# DoubleAmp.net
KiCad netlist of a schematic drawn in EAGLE
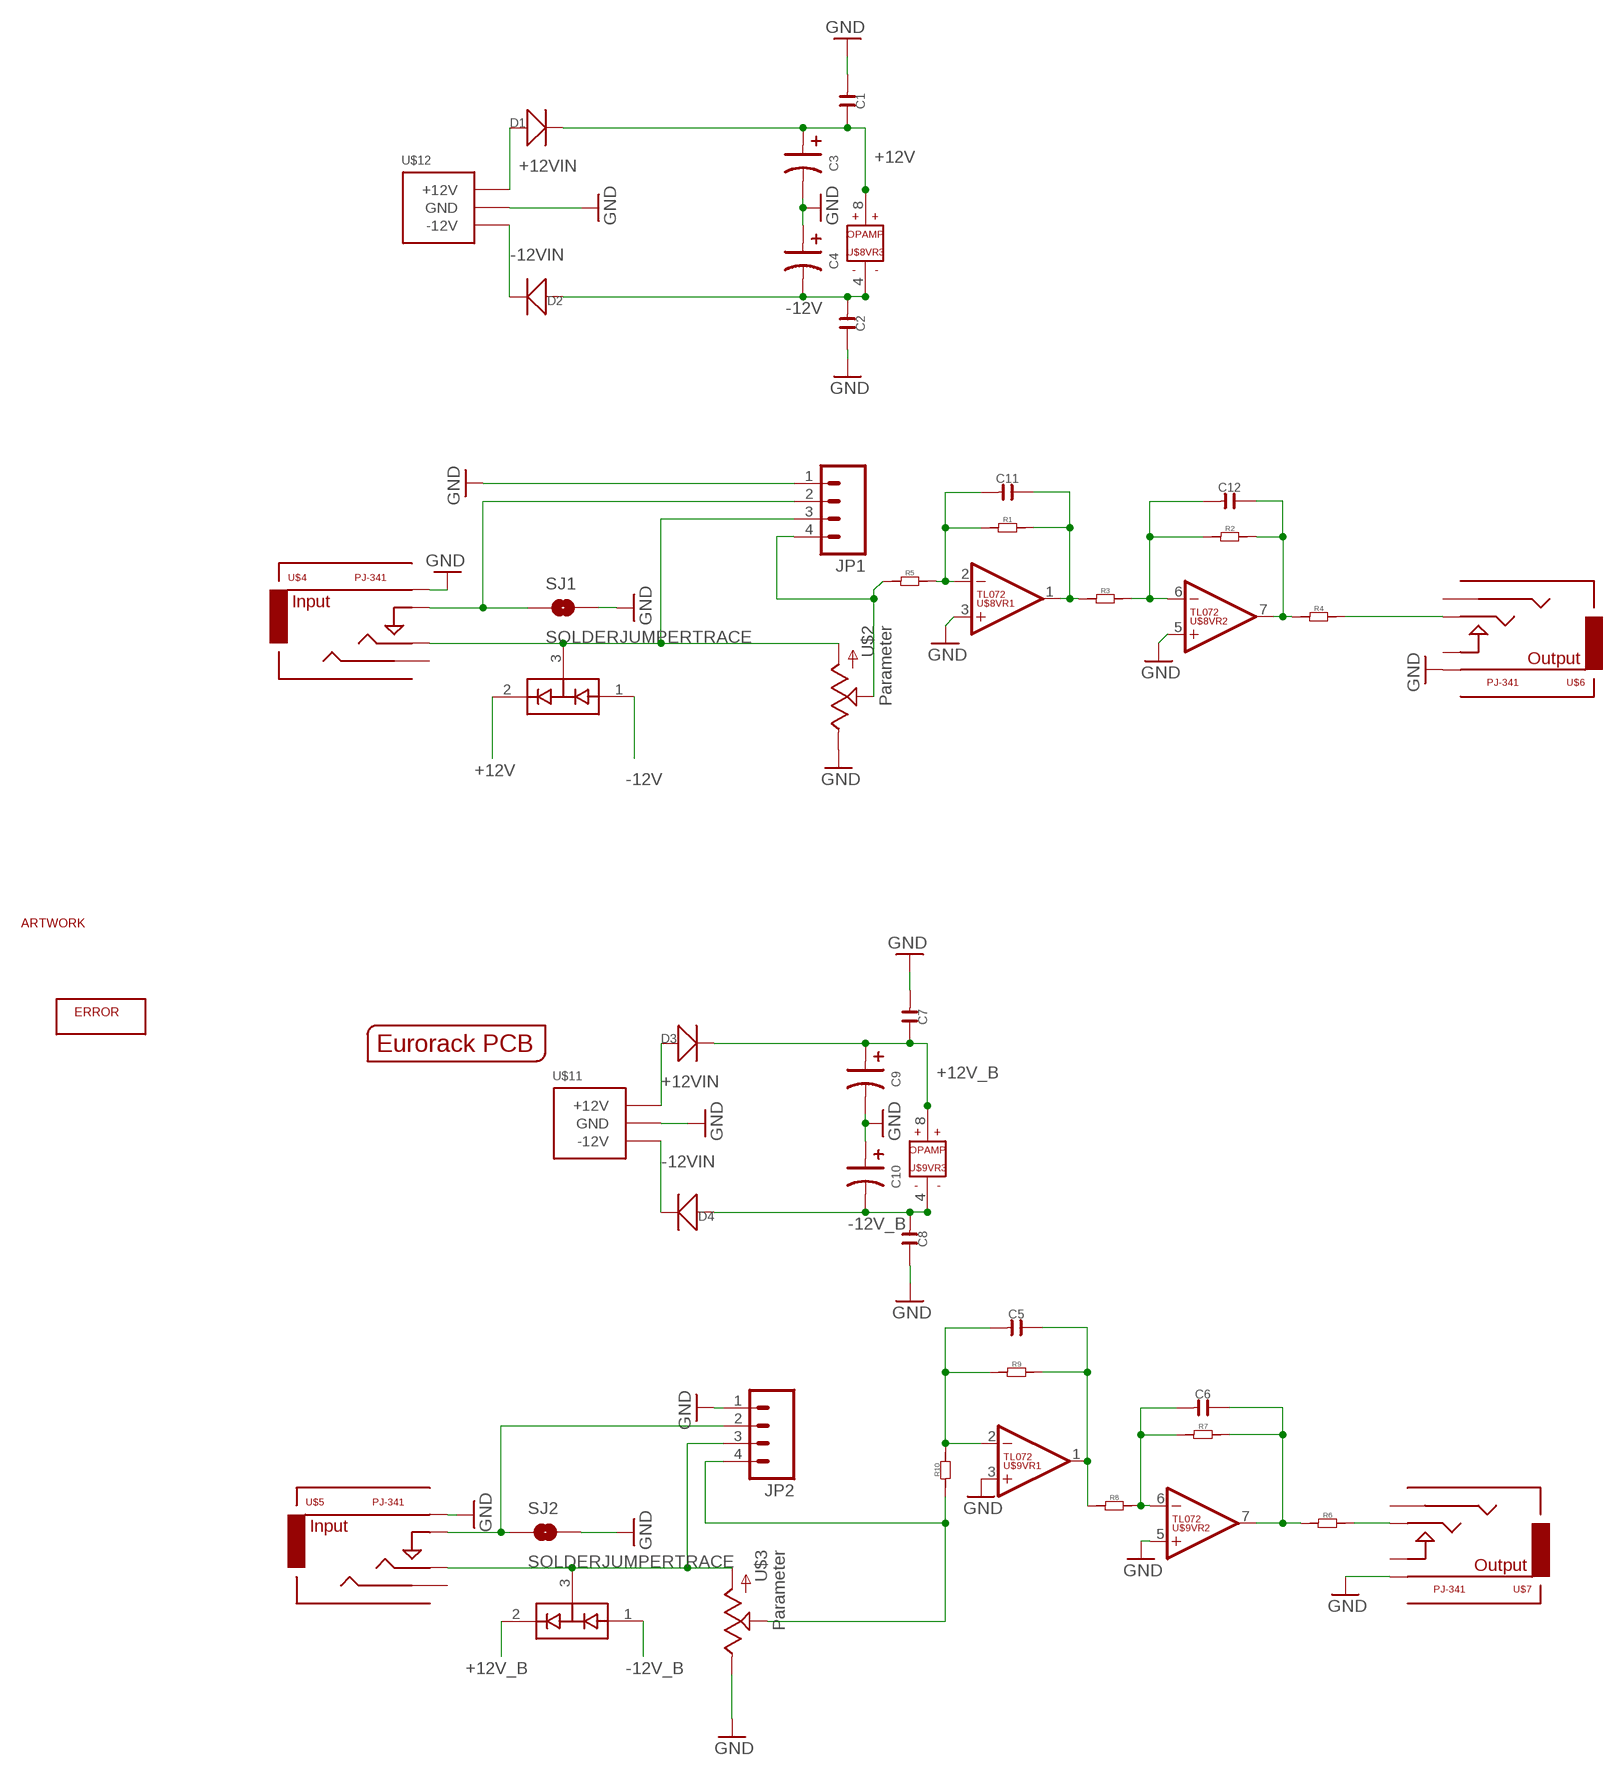
[diagram p0: schematic, sheet 1]

(export (version "E")
  (design (tool "Eeschema 10.0.6"))
  (components
    (comp (ref "C1")
      (value "C-0603")
      (footprint "eagle-import:C0603")
      (libsource (lib "eagle-import") (part "C-0603"))
    )
    (comp (ref "C2")
      (value "C-0603")
      (footprint "eagle-import:C0603")
      (libsource (lib "eagle-import") (part "C-0603"))
    )
    (comp (ref "C3")
      (value "C-POLAR-A")
      (footprint "eagle-import:AVX-A")
      (libsource (lib "eagle-import") (part "C-POLAR-A"))
    )
    (comp (ref "C4")
      (value "C-POLAR-A")
      (footprint "eagle-import:AVX-A")
      (libsource (lib "eagle-import") (part "C-POLAR-A"))
    )
    (comp (ref "C5")
      (value "C-0603")
      (footprint "eagle-import:C0603")
      (libsource (lib "eagle-import") (part "C-0603"))
    )
    (comp (ref "C6")
      (value "C-0603")
      (footprint "eagle-import:C0603")
      (libsource (lib "eagle-import") (part "C-0603"))
    )
    (comp (ref "C7")
      (value "C-0603")
      (footprint "eagle-import:C0603")
      (libsource (lib "eagle-import") (part "C-0603"))
    )
    (comp (ref "C8")
      (value "C-0603")
      (footprint "eagle-import:C0603")
      (libsource (lib "eagle-import") (part "C-0603"))
    )
    (comp (ref "C9")
      (value "C-POLAR-A")
      (footprint "eagle-import:AVX-A")
      (libsource (lib "eagle-import") (part "C-POLAR-A"))
    )
    (comp (ref "C10")
      (value "C-POLAR-A")
      (footprint "eagle-import:AVX-A")
      (libsource (lib "eagle-import") (part "C-POLAR-A"))
    )
    (comp (ref "C11")
      (value "C-0603")
      (footprint "eagle-import:C0603")
      (libsource (lib "eagle-import") (part "C-0603"))
    )
    (comp (ref "C12")
      (value "C-0603")
      (footprint "eagle-import:C0603")
      (libsource (lib "eagle-import") (part "C-0603"))
    )
    (comp (ref "D1")
      (value "D-SMA")
      (footprint "eagle-import:DO-214AC")
      (libsource (lib "eagle-import") (part "D-SMA"))
    )
    (comp (ref "D2")
      (value "D-SMA")
      (footprint "eagle-import:DO-214AC")
      (libsource (lib "eagle-import") (part "D-SMA"))
    )
    (comp (ref "D3")
      (value "D-SMA")
      (footprint "eagle-import:DO-214AC")
      (libsource (lib "eagle-import") (part "D-SMA"))
    )
    (comp (ref "D4")
      (value "D-SMA")
      (footprint "eagle-import:DO-214AC")
      (libsource (lib "eagle-import") (part "D-SMA"))
    )
    (comp (ref "D5")
      (value "BAV99")
      (footprint "eagle-import:SOT23")
      (libsource (lib "eagle-import") (part "BAV99"))
    )
    (comp (ref "D6")
      (value "BAV99")
      (footprint "eagle-import:SOT23")
      (libsource (lib "eagle-import") (part "BAV99"))
    )
    (comp (ref "JP1")
      (value "M04PTH")
      (footprint "eagle-import:1X04")
      (libsource (lib "eagle-import") (part "M04PTH"))
    )
    (comp (ref "JP2")
      (value "M04PTH")
      (footprint "eagle-import:1X04")
      (libsource (lib "eagle-import") (part "M04PTH"))
    )
    (comp (ref "R1")
      (value "R-0603")
      (footprint "eagle-import:R0603")
      (libsource (lib "eagle-import") (part "R-0603"))
    )
    (comp (ref "R2")
      (value "R-0603")
      (footprint "eagle-import:R0603")
      (libsource (lib "eagle-import") (part "R-0603"))
    )
    (comp (ref "R3")
      (value "R-0603")
      (footprint "eagle-import:R0603")
      (libsource (lib "eagle-import") (part "R-0603"))
    )
    (comp (ref "R4")
      (value "R-0603")
      (footprint "eagle-import:R0603")
      (libsource (lib "eagle-import") (part "R-0603"))
    )
    (comp (ref "R5")
      (value "R-0603")
      (footprint "eagle-import:R0603")
      (libsource (lib "eagle-import") (part "R-0603"))
    )
    (comp (ref "R6")
      (value "R-0603")
      (footprint "eagle-import:R0603")
      (libsource (lib "eagle-import") (part "R-0603"))
    )
    (comp (ref "R7")
      (value "R-0603")
      (footprint "eagle-import:R0603")
      (libsource (lib "eagle-import") (part "R-0603"))
    )
    (comp (ref "R8")
      (value "R-0603")
      (footprint "eagle-import:R0603")
      (libsource (lib "eagle-import") (part "R-0603"))
    )
    (comp (ref "R9")
      (value "R-0603")
      (footprint "eagle-import:R0603")
      (libsource (lib "eagle-import") (part "R-0603"))
    )
    (comp (ref "R10")
      (value "R-0603")
      (footprint "eagle-import:R0603")
      (libsource (lib "eagle-import") (part "R-0603"))
    )
    (comp (ref "SJ1")
      (value "SOLDERJUMPERTRACE")
      (footprint "eagle-import:SJ_2S-TRACE")
      (libsource (lib "eagle-import") (part "SOLDERJUMPERTRACE"))
    )
    (comp (ref "SJ2")
      (value "SOLDERJUMPERTRACE")
      (footprint "eagle-import:SJ_2S-TRACE")
      (libsource (lib "eagle-import") (part "SOLDERJUMPERTRACE"))
    )
    (comp (ref "U$1")
      (value "EURORACK_PCB4HP")
      (footprint "eagle-import:EURORACK4HPPCB")
      (libsource (lib "eagle-import") (part "EURORACK_PCB4HP"))
    )
    (comp (ref "U$2")
      (value "POTZEPHPOT")
      (footprint "eagle-import:OG-POTS_ALPS_POT_VERTICAL")
      (libsource (lib "eagle-import") (part "POTZEPHPOT"))
    )
    (comp (ref "U$3")
      (value "POTZEPHPOT")
      (footprint "eagle-import:OG-POTS_ALPS_POT_VERTICAL")
      (libsource (lib "eagle-import") (part "POTZEPHPOT"))
    )
    (comp (ref "U$4")
      (value "PJ-341")
      (footprint "eagle-import:3.5MM-JACK-SWITCH-13MM-INPUT")
      (libsource (lib "eagle-import") (part "AUDIO-JACKINPUT"))
    )
    (comp (ref "U$5")
      (value "PJ-341")
      (footprint "eagle-import:3.5MM-JACK-SWITCH-13MM-INPUT")
      (libsource (lib "eagle-import") (part "AUDIO-JACKINPUT"))
    )
    (comp (ref "U$6")
      (value "PJ-341")
      (footprint "eagle-import:3.5MM-JACK-SWITCH-13MM-OUTPUT")
      (libsource (lib "eagle-import") (part "AUDIO-JACKOUTPUT"))
    )
    (comp (ref "U$7")
      (value "PJ-341")
      (footprint "eagle-import:3.5MM-JACK-SWITCH-13MM-OUTPUT")
      (libsource (lib "eagle-import") (part "AUDIO-JACKOUTPUT"))
    )
    (comp (ref "U$8")
      (value "TL072")
      (footprint "eagle-import:SO08")
      (libsource (lib "eagle-import") (part "TL072"))
    )
    (comp (ref "U$9")
      (value "TL072")
      (footprint "eagle-import:SO08")
      (libsource (lib "eagle-import") (part "TL072"))
    )
    (comp (ref "U$10")
      (value "ERRORLOGOBIGGER")
      (footprint "eagle-import:ERRORLOGO_BIGGER")
      (libsource (lib "eagle-import") (part "ERRORLOGOBIGGER"))
    )
    (comp (ref "U$11")
      (value "POWER_SIMPLE")
      (footprint "eagle-import:2X05_SMT_HEADER")
      (libsource (lib "eagle-import") (part "POWER_SIMPLE"))
    )
    (comp (ref "U$12")
      (value "POWER_SIMPLE")
      (footprint "eagle-import:2X05_SMT_HEADER")
      (libsource (lib "eagle-import") (part "POWER_SIMPLE"))
    )
    (comp (ref "U$13")
      (value "TINRS_ARTWORKROCKET")
      (footprint "eagle-import:TINRS_ROCKET")
      (libsource (lib "eagle-import") (part "TINRS_ARTWORKROCKET"))
    )
  )
  (nets
    (net (code "1") (name "/+12V") (class "Default")
      (node (ref "C1") (pin "2") (pinfunction "2_2") (pintype "bidirectional"))
      (node (ref "C3") (pin "+") (pinfunction "1_+") (pintype "bidirectional"))
      (node (ref "D1") (pin "2") (pinfunction "-_2") (pintype "passive"))
      (node (ref "D6") (pin "2") (pinfunction "C2_2") (pintype "bidirectional"))
      (node (ref "U$8") (pin "8") (pinfunction "V+_8") (pintype "power_in"))
    )
    (net (code "2") (name "/+12VIN") (class "Default")
      (node (ref "D1") (pin "1") (pinfunction "+_1") (pintype "passive"))
      (node (ref "D3") (pin "1") (pinfunction "+_1") (pintype "passive"))
      (node (ref "U$11") (pin "10") (pinfunction "+12V_10") (pintype "bidirectional"))
      (node (ref "U$11") (pin "9") (pinfunction "+12V_9") (pintype "bidirectional"))
      (node (ref "U$12") (pin "10") (pinfunction "+12V_10") (pintype "bidirectional"))
      (node (ref "U$12") (pin "9") (pinfunction "+12V_9") (pintype "bidirectional"))
    )
    (net (code "3") (name "/+12V_B") (class "Default")
      (node (ref "C7") (pin "2") (pinfunction "2_2") (pintype "bidirectional"))
      (node (ref "C9") (pin "+") (pinfunction "1_+") (pintype "bidirectional"))
      (node (ref "D3") (pin "2") (pinfunction "-_2") (pintype "passive"))
      (node (ref "D5") (pin "2") (pinfunction "C2_2") (pintype "bidirectional"))
      (node (ref "U$9") (pin "8") (pinfunction "V+_8") (pintype "power_in"))
    )
    (net (code "4") (name "/-12V") (class "Default")
      (node (ref "C2") (pin "1") (pinfunction "1_1") (pintype "bidirectional"))
      (node (ref "C4") (pin "-") (pinfunction "2_-") (pintype "bidirectional"))
      (node (ref "D2") (pin "1") (pinfunction "+_1") (pintype "passive"))
      (node (ref "D6") (pin "1") (pinfunction "A1_1") (pintype "bidirectional"))
      (node (ref "U$8") (pin "4") (pinfunction "V-_4") (pintype "power_in"))
    )
    (net (code "5") (name "/-12VIN") (class "Default")
      (node (ref "D2") (pin "2") (pinfunction "-_2") (pintype "passive"))
      (node (ref "D4") (pin "2") (pinfunction "-_2") (pintype "passive"))
      (node (ref "U$11") (pin "1") (pinfunction "-12V_1") (pintype "bidirectional"))
      (node (ref "U$11") (pin "2") (pinfunction "-12V_2") (pintype "bidirectional"))
      (node (ref "U$12") (pin "1") (pinfunction "-12V_1") (pintype "bidirectional"))
      (node (ref "U$12") (pin "2") (pinfunction "-12V_2") (pintype "bidirectional"))
    )
    (net (code "6") (name "/-12V_B") (class "Default")
      (node (ref "C10") (pin "-") (pinfunction "2_-") (pintype "bidirectional"))
      (node (ref "C8") (pin "1") (pinfunction "1_1") (pintype "bidirectional"))
      (node (ref "D4") (pin "1") (pinfunction "+_1") (pintype "passive"))
      (node (ref "D5") (pin "1") (pinfunction "A1_1") (pintype "bidirectional"))
      (node (ref "U$9") (pin "4") (pinfunction "V-_4") (pintype "power_in"))
    )
    (net (code "7") (name "GND") (class "Default")
      (node (ref "C1") (pin "1") (pinfunction "1_1") (pintype "bidirectional"))
      (node (ref "C10") (pin "+") (pinfunction "1_+") (pintype "bidirectional"))
      (node (ref "C2") (pin "2") (pinfunction "2_2") (pintype "bidirectional"))
      (node (ref "C3") (pin "-") (pinfunction "2_-") (pintype "bidirectional"))
      (node (ref "C4") (pin "+") (pinfunction "1_+") (pintype "bidirectional"))
      (node (ref "C7") (pin "1") (pinfunction "1_1") (pintype "bidirectional"))
      (node (ref "C8") (pin "2") (pinfunction "2_2") (pintype "bidirectional"))
      (node (ref "C9") (pin "-") (pinfunction "2_-") (pintype "bidirectional"))
      (node (ref "JP1") (pin "1") (pinfunction "1_1") (pintype "passive"))
      (node (ref "JP2") (pin "1") (pinfunction "1_1") (pintype "passive"))
      (node (ref "SJ1") (pin "2") (pinfunction "2_2") (pintype "passive"))
      (node (ref "SJ2") (pin "2") (pinfunction "2_2") (pintype "passive"))
      (node (ref "U$11") (pin "3") (pinfunction "GND_3") (pintype "bidirectional"))
      (node (ref "U$11") (pin "4") (pinfunction "GND_4") (pintype "bidirectional"))
      (node (ref "U$11") (pin "5") (pinfunction "GND_5") (pintype "bidirectional"))
      (node (ref "U$11") (pin "6") (pinfunction "GND_6") (pintype "bidirectional"))
      (node (ref "U$11") (pin "7") (pinfunction "GND_7") (pintype "bidirectional"))
      (node (ref "U$11") (pin "8") (pinfunction "GND_8") (pintype "bidirectional"))
      (node (ref "U$12") (pin "3") (pinfunction "GND_3") (pintype "bidirectional"))
      (node (ref "U$12") (pin "4") (pinfunction "GND_4") (pintype "bidirectional"))
      (node (ref "U$12") (pin "5") (pinfunction "GND_5") (pintype "bidirectional"))
      (node (ref "U$12") (pin "6") (pinfunction "GND_6") (pintype "bidirectional"))
      (node (ref "U$12") (pin "7") (pinfunction "GND_7") (pintype "bidirectional"))
      (node (ref "U$12") (pin "8") (pinfunction "GND_8") (pintype "bidirectional"))
      (node (ref "U$2") (pin "P$1") (pinfunction "E_P$1") (pintype "passive"))
      (node (ref "U$3") (pin "P$1") (pinfunction "E_P$1") (pintype "passive"))
      (node (ref "U$4") (pin "RING@3") (pinfunction "RING_RING@3") (pintype "bidirectional"))
      (node (ref "U$5") (pin "RING@3") (pinfunction "RING_RING@3") (pintype "bidirectional"))
      (node (ref "U$6") (pin "RING@3") (pinfunction "RING_RING@3") (pintype "bidirectional"))
      (node (ref "U$7") (pin "RING@3") (pinfunction "RING_RING@3") (pintype "bidirectional"))
      (node (ref "U$8") (pin "3") (pinfunction "+IN_3") (pintype "input"))
      (node (ref "U$8") (pin "5") (pinfunction "+IN_5") (pintype "input"))
      (node (ref "U$9") (pin "3") (pinfunction "+IN_3") (pintype "input"))
      (node (ref "U$9") (pin "5") (pinfunction "+IN_5") (pintype "input"))
    )
    (net (code "8") (name "Net-(D5-COM)") (class "Default")
      (node (ref "D5") (pin "3") (pinfunction "COM_3") (pintype "bidirectional"))
      (node (ref "JP2") (pin "3") (pinfunction "3_3") (pintype "passive"))
      (node (ref "U$3") (pin "P$3") (pinfunction "A_P$3") (pintype "passive"))
      (node (ref "U$5") (pin "TIP@3") (pinfunction "TIP_TIP@3") (pintype "bidirectional"))
    )
    (net (code "9") (name "Net-(D6-COM)") (class "Default")
      (node (ref "D6") (pin "3") (pinfunction "COM_3") (pintype "bidirectional"))
      (node (ref "JP1") (pin "3") (pinfunction "3_3") (pintype "passive"))
      (node (ref "U$2") (pin "P$3") (pinfunction "A_P$3") (pintype "passive"))
      (node (ref "U$4") (pin "TIP@3") (pinfunction "TIP_TIP@3") (pintype "bidirectional"))
    )
    (net (code "10") (name "Net-(U$2-S)") (class "Default")
      (node (ref "JP1") (pin "4") (pinfunction "4_4") (pintype "passive"))
      (node (ref "R5") (pin "1") (pinfunction "1_1") (pintype "bidirectional"))
      (node (ref "U$2") (pin "P$2") (pinfunction "S_P$2") (pintype "passive"))
    )
    (net (code "11") (name "Net-(U$3-S)") (class "Default")
      (node (ref "JP2") (pin "4") (pinfunction "4_4") (pintype "passive"))
      (node (ref "R10") (pin "1") (pinfunction "1_1") (pintype "bidirectional"))
      (node (ref "U$3") (pin "P$2") (pinfunction "S_P$2") (pintype "passive"))
    )
    (net (code "12") (name "Net-(U$4-SWITCH)") (class "Default")
      (node (ref "JP1") (pin "2") (pinfunction "2_2") (pintype "passive"))
      (node (ref "SJ1") (pin "1") (pinfunction "1_1") (pintype "passive"))
      (node (ref "U$4") (pin "SWITCH@3") (pinfunction "SWITCH_SWITCH@3") (pintype "bidirectional"))
    )
    (net (code "13") (name "Net-(U$5-SWITCH)") (class "Default")
      (node (ref "JP2") (pin "2") (pinfunction "2_2") (pintype "passive"))
      (node (ref "SJ2") (pin "1") (pinfunction "1_1") (pintype "passive"))
      (node (ref "U$5") (pin "SWITCH@3") (pinfunction "SWITCH_SWITCH@3") (pintype "bidirectional"))
    )
    (net (code "14") (name "Net-(U$6-TIP)") (class "Default")
      (node (ref "R4") (pin "2") (pinfunction "2_2") (pintype "bidirectional"))
      (node (ref "U$6") (pin "TIP@3") (pinfunction "TIP_TIP@3") (pintype "bidirectional"))
    )
    (net (code "15") (name "Net-(U$7-TIP)") (class "Default")
      (node (ref "R6") (pin "2") (pinfunction "2_2") (pintype "bidirectional"))
      (node (ref "U$7") (pin "TIP@3") (pinfunction "TIP_TIP@3") (pintype "bidirectional"))
    )
    (net (code "16") (name "Net-(U$8A--IN)") (class "Default")
      (node (ref "C11") (pin "1") (pinfunction "1_1") (pintype "bidirectional"))
      (node (ref "R1") (pin "1") (pinfunction "1_1") (pintype "bidirectional"))
      (node (ref "R5") (pin "2") (pinfunction "2_2") (pintype "bidirectional"))
      (node (ref "U$8") (pin "2") (pinfunction "-IN_2") (pintype "input"))
    )
    (net (code "17") (name "Net-(U$8A-OUT)") (class "Default")
      (node (ref "C11") (pin "2") (pinfunction "2_2") (pintype "bidirectional"))
      (node (ref "R1") (pin "2") (pinfunction "2_2") (pintype "bidirectional"))
      (node (ref "R3") (pin "1") (pinfunction "1_1") (pintype "bidirectional"))
      (node (ref "U$8") (pin "1") (pinfunction "OUT_1") (pintype "output"))
    )
    (net (code "18") (name "Net-(U$8B--IN)") (class "Default")
      (node (ref "C12") (pin "1") (pinfunction "1_1") (pintype "bidirectional"))
      (node (ref "R2") (pin "1") (pinfunction "1_1") (pintype "bidirectional"))
      (node (ref "R3") (pin "2") (pinfunction "2_2") (pintype "bidirectional"))
      (node (ref "U$8") (pin "6") (pinfunction "-IN_6") (pintype "input"))
    )
    (net (code "19") (name "Net-(U$8B-OUT)") (class "Default")
      (node (ref "C12") (pin "2") (pinfunction "2_2") (pintype "bidirectional"))
      (node (ref "R2") (pin "2") (pinfunction "2_2") (pintype "bidirectional"))
      (node (ref "R4") (pin "1") (pinfunction "1_1") (pintype "bidirectional"))
      (node (ref "U$8") (pin "7") (pinfunction "OUT_7") (pintype "output"))
    )
    (net (code "20") (name "Net-(U$9A--IN)") (class "Default")
      (node (ref "C5") (pin "1") (pinfunction "1_1") (pintype "bidirectional"))
      (node (ref "R10") (pin "2") (pinfunction "2_2") (pintype "bidirectional"))
      (node (ref "R9") (pin "1") (pinfunction "1_1") (pintype "bidirectional"))
      (node (ref "U$9") (pin "2") (pinfunction "-IN_2") (pintype "input"))
    )
    (net (code "21") (name "Net-(U$9A-OUT)") (class "Default")
      (node (ref "C5") (pin "2") (pinfunction "2_2") (pintype "bidirectional"))
      (node (ref "R8") (pin "1") (pinfunction "1_1") (pintype "bidirectional"))
      (node (ref "R9") (pin "2") (pinfunction "2_2") (pintype "bidirectional"))
      (node (ref "U$9") (pin "1") (pinfunction "OUT_1") (pintype "output"))
    )
    (net (code "22") (name "Net-(U$9B--IN)") (class "Default")
      (node (ref "C6") (pin "1") (pinfunction "1_1") (pintype "bidirectional"))
      (node (ref "R7") (pin "1") (pinfunction "1_1") (pintype "bidirectional"))
      (node (ref "R8") (pin "2") (pinfunction "2_2") (pintype "bidirectional"))
      (node (ref "U$9") (pin "6") (pinfunction "-IN_6") (pintype "input"))
    )
    (net (code "23") (name "Net-(U$9B-OUT)") (class "Default")
      (node (ref "C6") (pin "2") (pinfunction "2_2") (pintype "bidirectional"))
      (node (ref "R6") (pin "1") (pinfunction "1_1") (pintype "bidirectional"))
      (node (ref "R7") (pin "2") (pinfunction "2_2") (pintype "bidirectional"))
      (node (ref "U$9") (pin "7") (pinfunction "OUT_7") (pintype "output"))
    )
    (net (code "24") (name "unconnected-(U$4-SECOND-PadSECOND@3)") (class "Default")
      (node (ref "U$4") (pin "SECOND@3") (pinfunction "SECOND_SECOND@3") (pintype "bidirectional"))
    )
    (net (code "25") (name "unconnected-(U$5-SECOND-PadSECOND@3)") (class "Default")
      (node (ref "U$5") (pin "SECOND@3") (pinfunction "SECOND_SECOND@3") (pintype "bidirectional"))
    )
    (net (code "26") (name "unconnected-(U$6-SECOND-PadSECOND@3)") (class "Default")
      (node (ref "U$6") (pin "SECOND@3") (pinfunction "SECOND_SECOND@3") (pintype "bidirectional"))
    )
    (net (code "27") (name "unconnected-(U$6-SWITCH-PadSWITCH@3)") (class "Default")
      (node (ref "U$6") (pin "SWITCH@3") (pinfunction "SWITCH_SWITCH@3") (pintype "bidirectional"))
    )
    (net (code "28") (name "unconnected-(U$7-SECOND-PadSECOND@3)") (class "Default")
      (node (ref "U$7") (pin "SECOND@3") (pinfunction "SECOND_SECOND@3") (pintype "bidirectional"))
    )
    (net (code "29") (name "unconnected-(U$7-SWITCH-PadSWITCH@3)") (class "Default")
      (node (ref "U$7") (pin "SWITCH@3") (pinfunction "SWITCH_SWITCH@3") (pintype "bidirectional"))
    )
  )
)
